# bluz_gw_v1.net
KiCad netlist of a schematic drawn in EAGLE
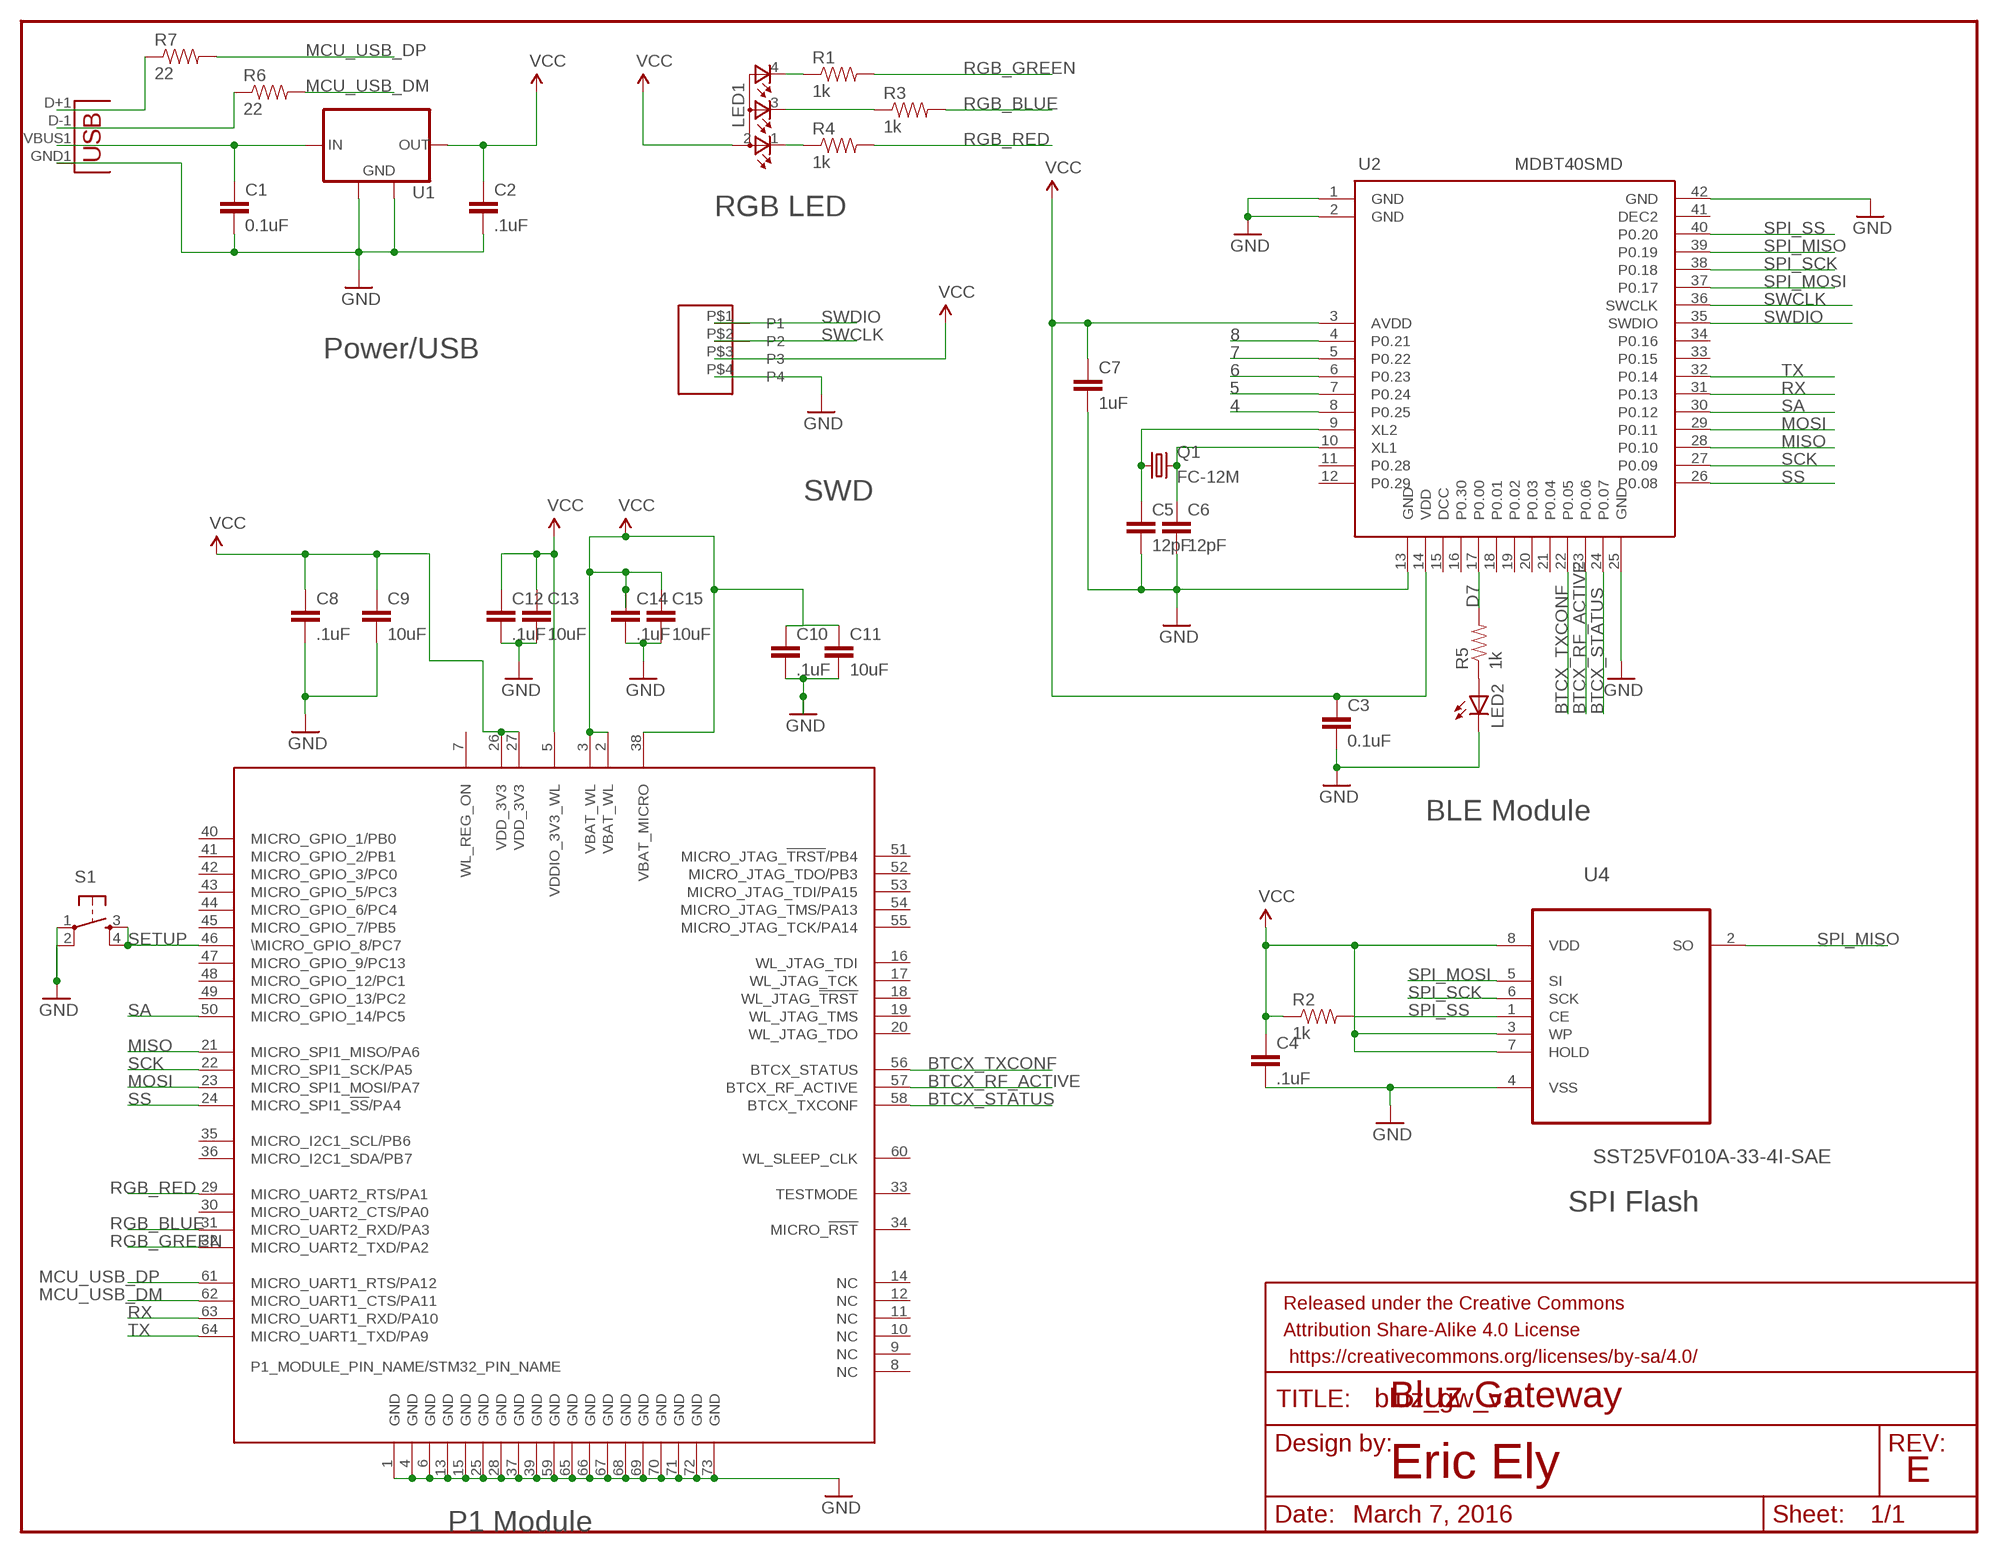
[diagram p0: schematic, sheet 1]

(export (version "E")
  (design (tool "Eeschema 10.0.6"))
  (components
    (comp (ref "C1")
      (value "0.1uF")
      (footprint "eagle-import:0603-CAP")
      (libsource (lib "eagle-import") (part "SparkFun-Passives_CAP0603-CAP"))
    )
    (comp (ref "C2")
      (value ".1uF")
      (footprint "eagle-import:0603-CAP")
      (libsource (lib "eagle-import") (part "CAP0603-CAP"))
    )
    (comp (ref "C3")
      (value "0.1uF")
      (footprint "eagle-import:0603-CAP")
      (libsource (lib "eagle-import") (part "CAP0603-CAP"))
    )
    (comp (ref "C4")
      (value ".1uF")
      (footprint "eagle-import:0603-CAP")
      (libsource (lib "eagle-import") (part "CAP0603-CAP"))
    )
    (comp (ref "C5")
      (value "12pF")
      (footprint "eagle-import:0603-CAP")
      (libsource (lib "eagle-import") (part "SparkFun-Passives_CAP0603-CAP"))
    )
    (comp (ref "C6")
      (value "12pF")
      (footprint "eagle-import:0603-CAP")
      (libsource (lib "eagle-import") (part "SparkFun-Passives_CAP0603-CAP"))
    )
    (comp (ref "C7")
      (value "1uF")
      (footprint "eagle-import:0603-CAP")
      (libsource (lib "eagle-import") (part "CAP0603-CAP"))
    )
    (comp (ref "C8")
      (value ".1uF")
      (footprint "eagle-import:0603-CAP")
      (libsource (lib "eagle-import") (part "CAP0603-CAP"))
    )
    (comp (ref "C9")
      (value "10uF")
      (footprint "eagle-import:0603-CAP")
      (libsource (lib "eagle-import") (part "CAP0603-CAP"))
    )
    (comp (ref "C10")
      (value ".1uF")
      (footprint "eagle-import:0603-CAP")
      (libsource (lib "eagle-import") (part "CAP0603-CAP"))
    )
    (comp (ref "C11")
      (value "10uF")
      (footprint "eagle-import:0603-CAP")
      (libsource (lib "eagle-import") (part "CAP0603-CAP"))
    )
    (comp (ref "C12")
      (value ".1uF")
      (footprint "eagle-import:0603-CAP")
      (libsource (lib "eagle-import") (part "CAP0603-CAP"))
    )
    (comp (ref "C13")
      (value "10uF")
      (footprint "eagle-import:0603-CAP")
      (libsource (lib "eagle-import") (part "CAP0603-CAP"))
    )
    (comp (ref "C14")
      (value ".1uF")
      (footprint "eagle-import:0603-CAP")
      (libsource (lib "eagle-import") (part "CAP0603-CAP"))
    )
    (comp (ref "C15")
      (value "10uF")
      (footprint "eagle-import:0603-CAP")
      (libsource (lib "eagle-import") (part "CAP0603-CAP"))
    )
    (comp (ref "FRAME1")
      (value "FRAME-LETTER")
      (footprint "eagle-import:CREATIVE_COMMONS")
      (libsource (lib "eagle-import") (part "FRAME-LETTER"))
    )
    (comp (ref "JP2")
      (value "USBA-SMD-MALE")
      (footprint "eagle-import:USB-A-SMT-MALE")
      (libsource (lib "eagle-import") (part "USBA-SMD-MALE"))
    )
    (comp (ref "LED1")
      (value "TOPLED-3PLCC")
      (footprint "eagle-import:P-LCC-4-3")
      (libsource (lib "eagle-import") (part "TOPLED-3PLCC"))
    )
    (comp (ref "LED2")
      (value "LEDCHIP-LED0603")
      (footprint "eagle-import:CHIP-LED0603")
      (libsource (lib "eagle-import") (part "LEDCHIP-LED0603"))
    )
    (comp (ref "Q1")
      (value "FC-12M")
      (footprint "eagle-import:FC-12M")
      (libsource (lib "eagle-import") (part "FC-12M"))
    )
    (comp (ref "R1")
      (value "1k")
      (footprint "eagle-import:0603-RES")
      (libsource (lib "eagle-import") (part "RESISTOR0603-RES"))
    )
    (comp (ref "R2")
      (value "1k")
      (footprint "eagle-import:0603-RES")
      (libsource (lib "eagle-import") (part "RESISTOR0603-RES"))
    )
    (comp (ref "R3")
      (value "1k")
      (footprint "eagle-import:0603-RES")
      (libsource (lib "eagle-import") (part "RESISTOR0603-RES"))
    )
    (comp (ref "R4")
      (value "1k")
      (footprint "eagle-import:0603-RES")
      (libsource (lib "eagle-import") (part "RESISTOR0603-RES"))
    )
    (comp (ref "R5")
      (value "1k")
      (footprint "eagle-import:0603-RES")
      (libsource (lib "eagle-import") (part "RESISTOR0603-RES"))
    )
    (comp (ref "R6")
      (value "22")
      (footprint "eagle-import:0603-RES")
      (libsource (lib "eagle-import") (part "RESISTOR0603-RES"))
    )
    (comp (ref "R7")
      (value "22")
      (footprint "eagle-import:0603-RES")
      (libsource (lib "eagle-import") (part "RESISTOR0603-RES"))
    )
    (comp (ref "S1")
      (value "TAC_SWITCHSMD")
      (footprint "eagle-import:TACTILE_SWITCH_SMD")
      (libsource (lib "eagle-import") (part "TAC_SWITCHSMD"))
    )
    (comp (ref "U$3")
      (value "POGO_CONNECTORPOGO_CONNECTOR")
      (footprint "eagle-import:POGO_CONNECTER")
      (libsource (lib "eagle-import") (part "POGO_CONNECTORPOGO_CONNECTOR"))
    )
    (comp (ref "U1")
      (value "MCP1825S-SOT223")
      (footprint "eagle-import:SOT223")
      (libsource (lib "eagle-import") (part "MCP1825S-SOT223"))
    )
    (comp (ref "U2")
      (value "MDBT40SMD")
      (footprint "eagle-import:MDBT40")
      (libsource (lib "eagle-import") (part "MDBT40SMD"))
    )
    (comp (ref "U3")
      (value "WM-N-BM-14")
      (footprint "eagle-import:WM-N-BM-14")
      (libsource (lib "eagle-import") (part "WM-N-BM-14"))
    )
    (comp (ref "U4")
      (value "SST25VF010A-33-4I-SAE")
      (footprint "eagle-import:SOIC127P600X175-8N")
      (libsource (lib "eagle-import") (part "SST25VF010A-33-4I-SAE"))
    )
  )
  (nets
    (net (code "1") (name "/4") (class "Default")
      (node (ref "U2") (pin "8") (pinfunction "P0.25_8") (pintype "bidirectional"))
    )
    (net (code "2") (name "/5") (class "Default")
      (node (ref "U2") (pin "7") (pinfunction "P0.24_7") (pintype "bidirectional"))
    )
    (net (code "3") (name "/6") (class "Default")
      (node (ref "U2") (pin "6") (pinfunction "P0.23_6") (pintype "bidirectional"))
    )
    (net (code "4") (name "/7") (class "Default")
      (node (ref "U2") (pin "5") (pinfunction "P0.22_5") (pintype "bidirectional"))
    )
    (net (code "5") (name "/8") (class "Default")
      (node (ref "U2") (pin "4") (pinfunction "P0.21_4") (pintype "bidirectional"))
    )
    (net (code "6") (name "/BTCX_RF_ACTIVE") (class "Default")
      (node (ref "U2") (pin "23") (pinfunction "P0.06_23") (pintype "bidirectional"))
      (node (ref "U3") (pin "57") (pinfunction "BTCX_RF_ACTIVE_57") (pintype "bidirectional"))
    )
    (net (code "7") (name "/BTCX_STATUS") (class "Default")
      (node (ref "U2") (pin "24") (pinfunction "P0.07_24") (pintype "bidirectional"))
      (node (ref "U3") (pin "58") (pinfunction "BTCX_TXCONF_58") (pintype "bidirectional"))
    )
    (net (code "8") (name "/BTCX_TXCONF") (class "Default")
      (node (ref "U2") (pin "22") (pinfunction "P0.05_22") (pintype "bidirectional"))
      (node (ref "U3") (pin "56") (pinfunction "BTCX_STATUS_56") (pintype "bidirectional"))
    )
    (net (code "9") (name "/D7") (class "Default")
      (node (ref "R5") (pin "2") (pinfunction "2_2") (pintype "passive"))
      (node (ref "U2") (pin "17") (pinfunction "P0.00_17") (pintype "bidirectional"))
    )
    (net (code "10") (name "/MCU_USB_DM") (class "Default")
      (node (ref "R6") (pin "2") (pinfunction "2_2") (pintype "passive"))
      (node (ref "U3") (pin "62") (pinfunction "MICRO_UART1_CTS/PA11_62") (pintype "bidirectional"))
    )
    (net (code "11") (name "/MCU_USB_DP") (class "Default")
      (node (ref "R7") (pin "2") (pinfunction "2_2") (pintype "passive"))
      (node (ref "U3") (pin "61") (pinfunction "MICRO_UART1_RTS/PA12_61") (pintype "bidirectional"))
    )
    (net (code "12") (name "/MISO") (class "Default")
      (node (ref "U2") (pin "28") (pinfunction "P0.10_28") (pintype "bidirectional"))
      (node (ref "U3") (pin "21") (pinfunction "MICRO_SPI1_MISO/PA6_21") (pintype "bidirectional"))
    )
    (net (code "13") (name "/MOSI") (class "Default")
      (node (ref "U2") (pin "29") (pinfunction "P0.11_29") (pintype "bidirectional"))
      (node (ref "U3") (pin "23") (pinfunction "MICRO_SPI1_MOSI/PA7_23") (pintype "bidirectional"))
    )
    (net (code "14") (name "/RGB_BLUE") (class "Default")
      (node (ref "R3") (pin "2") (pinfunction "2_2") (pintype "passive"))
      (node (ref "U3") (pin "31") (pinfunction "MICRO_UART2_RXD/PA3_31") (pintype "bidirectional"))
    )
    (net (code "15") (name "/RGB_GREEN") (class "Default")
      (node (ref "R1") (pin "2") (pinfunction "2_2") (pintype "passive"))
      (node (ref "U3") (pin "32") (pinfunction "MICRO_UART2_TXD/PA2_32") (pintype "bidirectional"))
    )
    (net (code "16") (name "/RGB_RED") (class "Default")
      (node (ref "R4") (pin "2") (pinfunction "2_2") (pintype "passive"))
      (node (ref "U3") (pin "29") (pinfunction "MICRO_UART2_RTS/PA1_29") (pintype "bidirectional"))
    )
    (net (code "17") (name "/RX") (class "Default")
      (node (ref "U2") (pin "31") (pinfunction "P0.13_31") (pintype "bidirectional"))
      (node (ref "U3") (pin "63") (pinfunction "MICRO_UART1_RXD/PA10_63") (pintype "bidirectional"))
    )
    (net (code "18") (name "/SA") (class "Default")
      (node (ref "U2") (pin "30") (pinfunction "P0.12_30") (pintype "bidirectional"))
      (node (ref "U3") (pin "50") (pinfunction "MICRO_GPIO_14/PC5_50") (pintype "bidirectional"))
    )
    (net (code "19") (name "/SCK") (class "Default")
      (node (ref "U2") (pin "27") (pinfunction "P0.09_27") (pintype "bidirectional"))
      (node (ref "U3") (pin "22") (pinfunction "MICRO_SPI1_SCK/PA5_22") (pintype "bidirectional"))
    )
    (net (code "20") (name "/SETUP") (class "Default")
      (node (ref "S1") (pin "3") (pinfunction "3_3") (pintype "passive"))
      (node (ref "S1") (pin "4") (pinfunction "4_4") (pintype "passive"))
      (node (ref "U3") (pin "46") (pinfunction "\\MICRO_GPIO_8/PC7_46") (pintype "bidirectional"))
    )
    (net (code "21") (name "/SPI_MISO") (class "Default")
      (node (ref "U2") (pin "39") (pinfunction "P0.19_39") (pintype "bidirectional"))
      (node (ref "U4") (pin "2") (pinfunction "SO_2") (pintype "output"))
    )
    (net (code "22") (name "/SPI_MOSI") (class "Default")
      (node (ref "U2") (pin "37") (pinfunction "P0.17_37") (pintype "bidirectional"))
      (node (ref "U4") (pin "5") (pinfunction "SI_5") (pintype "input"))
    )
    (net (code "23") (name "/SPI_SCK") (class "Default")
      (node (ref "U2") (pin "38") (pinfunction "P0.18_38") (pintype "bidirectional"))
      (node (ref "U4") (pin "6") (pinfunction "SCK_6") (pintype "input"))
    )
    (net (code "24") (name "/SPI_SS") (class "Default")
      (node (ref "R2") (pin "2") (pinfunction "2_2") (pintype "passive"))
      (node (ref "U2") (pin "40") (pinfunction "P0.20_40") (pintype "bidirectional"))
      (node (ref "U4") (pin "1") (pinfunction "CE_1") (pintype "input"))
    )
    (net (code "25") (name "/SS") (class "Default")
      (node (ref "U2") (pin "26") (pinfunction "P0.08_26") (pintype "bidirectional"))
      (node (ref "U3") (pin "24") (pinfunction "MICRO_SPI1_~{SS}/PA4_24") (pintype "bidirectional"))
    )
    (net (code "26") (name "/SWCLK") (class "Default")
      (node (ref "U$3") (pin "P$2") (pinfunction "P2_P$2") (pintype "bidirectional"))
      (node (ref "U2") (pin "36") (pinfunction "SWCLK_36") (pintype "bidirectional"))
    )
    (net (code "27") (name "/SWDIO") (class "Default")
      (node (ref "U$3") (pin "P$1") (pinfunction "P1_P$1") (pintype "bidirectional"))
      (node (ref "U2") (pin "35") (pinfunction "SWDIO_35") (pintype "bidirectional"))
    )
    (net (code "28") (name "/TX") (class "Default")
      (node (ref "U2") (pin "32") (pinfunction "P0.14_32") (pintype "bidirectional"))
      (node (ref "U3") (pin "64") (pinfunction "MICRO_UART1_TXD/PA9_64") (pintype "bidirectional"))
    )
    (net (code "29") (name "GND") (class "Default")
      (node (ref "C1") (pin "2") (pinfunction "2_2") (pintype "passive"))
      (node (ref "C10") (pin "2") (pinfunction "2_2") (pintype "passive"))
      (node (ref "C11") (pin "2") (pinfunction "2_2") (pintype "passive"))
      (node (ref "C12") (pin "2") (pinfunction "2_2") (pintype "passive"))
      (node (ref "C13") (pin "2") (pinfunction "2_2") (pintype "passive"))
      (node (ref "C14") (pin "2") (pinfunction "2_2") (pintype "passive"))
      (node (ref "C15") (pin "2") (pinfunction "2_2") (pintype "passive"))
      (node (ref "C2") (pin "2") (pinfunction "2_2") (pintype "passive"))
      (node (ref "C3") (pin "2") (pinfunction "2_2") (pintype "passive"))
      (node (ref "C4") (pin "2") (pinfunction "2_2") (pintype "passive"))
      (node (ref "C5") (pin "2") (pinfunction "2_2") (pintype "passive"))
      (node (ref "C6") (pin "2") (pinfunction "2_2") (pintype "passive"))
      (node (ref "C7") (pin "2") (pinfunction "2_2") (pintype "passive"))
      (node (ref "C8") (pin "2") (pinfunction "2_2") (pintype "passive"))
      (node (ref "C9") (pin "2") (pinfunction "2_2") (pintype "passive"))
      (node (ref "JP2") (pin "GND1") (pinfunction "GND_GND1") (pintype "bidirectional"))
      (node (ref "LED2") (pin "C") (pinfunction "C_C") (pintype "passive"))
      (node (ref "S1") (pin "1") (pinfunction "1_1") (pintype "passive"))
      (node (ref "S1") (pin "2") (pinfunction "2_2") (pintype "passive"))
      (node (ref "U$3") (pin "P$4") (pinfunction "P4_P$4") (pintype "bidirectional"))
      (node (ref "U1") (pin "2") (pinfunction "GND_2") (pintype "power_in"))
      (node (ref "U1") (pin "4") (pinfunction "GND_4") (pintype "power_in"))
      (node (ref "U2") (pin "1") (pinfunction "GND_1") (pintype "bidirectional"))
      (node (ref "U2") (pin "13") (pinfunction "GND_13") (pintype "bidirectional"))
      (node (ref "U2") (pin "2") (pinfunction "GND_2") (pintype "bidirectional"))
      (node (ref "U2") (pin "25") (pinfunction "GND_25") (pintype "bidirectional"))
      (node (ref "U2") (pin "42") (pinfunction "GND_42") (pintype "bidirectional"))
      (node (ref "U3") (pin "1") (pinfunction "GND_1") (pintype "bidirectional"))
      (node (ref "U3") (pin "13") (pinfunction "GND_13") (pintype "bidirectional"))
      (node (ref "U3") (pin "15") (pinfunction "GND_15") (pintype "bidirectional"))
      (node (ref "U3") (pin "25") (pinfunction "GND_25") (pintype "bidirectional"))
      (node (ref "U3") (pin "28") (pinfunction "GND_28") (pintype "bidirectional"))
      (node (ref "U3") (pin "37") (pinfunction "GND_37") (pintype "bidirectional"))
      (node (ref "U3") (pin "39") (pinfunction "GND_39") (pintype "bidirectional"))
      (node (ref "U3") (pin "4") (pinfunction "GND_4") (pintype "bidirectional"))
      (node (ref "U3") (pin "59") (pinfunction "GND_59") (pintype "bidirectional"))
      (node (ref "U3") (pin "6") (pinfunction "GND_6") (pintype "bidirectional"))
      (node (ref "U3") (pin "65") (pinfunction "GND_65") (pintype "bidirectional"))
      (node (ref "U3") (pin "66") (pinfunction "GND_66") (pintype "bidirectional"))
      (node (ref "U3") (pin "67") (pinfunction "GND_67") (pintype "bidirectional"))
      (node (ref "U3") (pin "68") (pinfunction "GND_68") (pintype "bidirectional"))
      (node (ref "U3") (pin "69") (pinfunction "GND_69") (pintype "bidirectional"))
      (node (ref "U3") (pin "70") (pinfunction "GND_70") (pintype "bidirectional"))
      (node (ref "U3") (pin "71") (pinfunction "GND_71") (pintype "bidirectional"))
      (node (ref "U3") (pin "72") (pinfunction "GND_72") (pintype "bidirectional"))
      (node (ref "U3") (pin "73") (pinfunction "GND_73") (pintype "bidirectional"))
      (node (ref "U4") (pin "4") (pinfunction "VSS_4") (pintype "passive"))
    )
    (net (code "30") (name "Net-(JP2-D+)") (class "Default")
      (node (ref "JP2") (pin "D+1") (pinfunction "D+_D+1") (pintype "bidirectional"))
      (node (ref "R7") (pin "1") (pinfunction "1_1") (pintype "passive"))
    )
    (net (code "31") (name "Net-(JP2-D-)") (class "Default")
      (node (ref "JP2") (pin "D-1") (pinfunction "D-_D-1") (pintype "bidirectional"))
      (node (ref "R6") (pin "1") (pinfunction "1_1") (pintype "passive"))
    )
    (net (code "32") (name "Net-(JP2-VBUS)") (class "Default")
      (node (ref "C1") (pin "1") (pinfunction "1_1") (pintype "passive"))
      (node (ref "JP2") (pin "VBUS1") (pinfunction "VBUS_VBUS1") (pintype "bidirectional"))
      (node (ref "U1") (pin "1") (pinfunction "IN_1") (pintype "input"))
    )
    (net (code "33") (name "Net-(LED1-CBLUE)") (class "Default")
      (node (ref "LED1") (pin "3") (pinfunction "CBLUE_3") (pintype "passive"))
      (node (ref "R3") (pin "1") (pinfunction "1_1") (pintype "passive"))
    )
    (net (code "34") (name "Net-(LED1-CGREEN)") (class "Default")
      (node (ref "LED1") (pin "4") (pinfunction "CGREEN_4") (pintype "passive"))
      (node (ref "R1") (pin "1") (pinfunction "1_1") (pintype "passive"))
    )
    (net (code "35") (name "Net-(LED1-CRED)") (class "Default")
      (node (ref "LED1") (pin "1") (pinfunction "CRED_1") (pintype "passive"))
      (node (ref "R4") (pin "1") (pinfunction "1_1") (pintype "passive"))
    )
    (net (code "36") (name "Net-(LED2-PadA)") (class "Default")
      (node (ref "LED2") (pin "A") (pinfunction "A_A") (pintype "passive"))
      (node (ref "R5") (pin "1") (pinfunction "1_1") (pintype "passive"))
    )
    (net (code "37") (name "Net-(U2-XL1)") (class "Default")
      (node (ref "C6") (pin "1") (pinfunction "1_1") (pintype "passive"))
      (node (ref "Q1") (pin "2") (pinfunction "2_2") (pintype "passive"))
      (node (ref "U2") (pin "10") (pinfunction "XL1_10") (pintype "bidirectional"))
    )
    (net (code "38") (name "Net-(U2-XL2)") (class "Default")
      (node (ref "C5") (pin "1") (pinfunction "1_1") (pintype "passive"))
      (node (ref "Q1") (pin "1") (pinfunction "1_1") (pintype "passive"))
      (node (ref "U2") (pin "9") (pinfunction "XL2_9") (pintype "bidirectional"))
    )
    (net (code "39") (name "VCC") (class "Default")
      (node (ref "C10") (pin "1") (pinfunction "1_1") (pintype "passive"))
      (node (ref "C11") (pin "1") (pinfunction "1_1") (pintype "passive"))
      (node (ref "C12") (pin "1") (pinfunction "1_1") (pintype "passive"))
      (node (ref "C13") (pin "1") (pinfunction "1_1") (pintype "passive"))
      (node (ref "C14") (pin "1") (pinfunction "1_1") (pintype "passive"))
      (node (ref "C15") (pin "1") (pinfunction "1_1") (pintype "passive"))
      (node (ref "C2") (pin "1") (pinfunction "1_1") (pintype "passive"))
      (node (ref "C3") (pin "1") (pinfunction "1_1") (pintype "passive"))
      (node (ref "C4") (pin "1") (pinfunction "1_1") (pintype "passive"))
      (node (ref "C7") (pin "1") (pinfunction "1_1") (pintype "passive"))
      (node (ref "C8") (pin "1") (pinfunction "1_1") (pintype "passive"))
      (node (ref "C9") (pin "1") (pinfunction "1_1") (pintype "passive"))
      (node (ref "LED1") (pin "2") (pinfunction "A2_2") (pintype "passive"))
      (node (ref "R2") (pin "1") (pinfunction "1_1") (pintype "passive"))
      (node (ref "U$3") (pin "P$3") (pinfunction "P3_P$3") (pintype "bidirectional"))
      (node (ref "U1") (pin "3") (pinfunction "OUT_3") (pintype "output"))
      (node (ref "U2") (pin "14") (pinfunction "VDD_14") (pintype "bidirectional"))
      (node (ref "U2") (pin "3") (pinfunction "AVDD_3") (pintype "bidirectional"))
      (node (ref "U3") (pin "2") (pinfunction "VBAT_WL_2") (pintype "bidirectional"))
      (node (ref "U3") (pin "26") (pinfunction "VDD_3V3_26") (pintype "bidirectional"))
      (node (ref "U3") (pin "27") (pinfunction "VDD_3V3_27") (pintype "bidirectional"))
      (node (ref "U3") (pin "3") (pinfunction "VBAT_WL_3") (pintype "bidirectional"))
      (node (ref "U3") (pin "38") (pinfunction "VBAT_MICRO_38") (pintype "bidirectional"))
      (node (ref "U3") (pin "5") (pinfunction "VDDIO_3V3_WL_5") (pintype "bidirectional"))
      (node (ref "U4") (pin "3") (pinfunction "WP_3") (pintype "input"))
      (node (ref "U4") (pin "7") (pinfunction "HOLD_7") (pintype "input"))
      (node (ref "U4") (pin "8") (pinfunction "VDD_8") (pintype "power_in"))
    )
    (net (code "40") (name "unconnected-(U2-DCC-Pad15)") (class "Default")
      (node (ref "U2") (pin "15") (pinfunction "DCC_15") (pintype "bidirectional"))
    )
    (net (code "41") (name "unconnected-(U2-DEC2-Pad41)") (class "Default")
      (node (ref "U2") (pin "41") (pinfunction "DEC2_41") (pintype "bidirectional"))
    )
    (net (code "42") (name "unconnected-(U2-P0.01-Pad18)") (class "Default")
      (node (ref "U2") (pin "18") (pinfunction "P0.01_18") (pintype "bidirectional"))
    )
    (net (code "43") (name "unconnected-(U2-P0.02-Pad19)") (class "Default")
      (node (ref "U2") (pin "19") (pinfunction "P0.02_19") (pintype "bidirectional"))
    )
    (net (code "44") (name "unconnected-(U2-P0.03-Pad20)") (class "Default")
      (node (ref "U2") (pin "20") (pinfunction "P0.03_20") (pintype "bidirectional"))
    )
    (net (code "45") (name "unconnected-(U2-P0.04-Pad21)") (class "Default")
      (node (ref "U2") (pin "21") (pinfunction "P0.04_21") (pintype "bidirectional"))
    )
    (net (code "46") (name "unconnected-(U2-P0.15-Pad33)") (class "Default")
      (node (ref "U2") (pin "33") (pinfunction "P0.15_33") (pintype "bidirectional"))
    )
    (net (code "47") (name "unconnected-(U2-P0.16-Pad34)") (class "Default")
      (node (ref "U2") (pin "34") (pinfunction "P0.16_34") (pintype "bidirectional"))
    )
    (net (code "48") (name "unconnected-(U2-P0.28-Pad11)") (class "Default")
      (node (ref "U2") (pin "11") (pinfunction "P0.28_11") (pintype "bidirectional"))
    )
    (net (code "49") (name "unconnected-(U2-P0.29-Pad12)") (class "Default")
      (node (ref "U2") (pin "12") (pinfunction "P0.29_12") (pintype "bidirectional"))
    )
    (net (code "50") (name "unconnected-(U2-P0.30-Pad16)") (class "Default")
      (node (ref "U2") (pin "16") (pinfunction "P0.30_16") (pintype "bidirectional"))
    )
    (net (code "51") (name "unconnected-(U3-MICRO_GPIO_1{slash}PB0-Pad40)") (class "Default")
      (node (ref "U3") (pin "40") (pinfunction "MICRO_GPIO_1/PB0_40") (pintype "bidirectional"))
    )
    (net (code "52") (name "unconnected-(U3-MICRO_GPIO_2{slash}PB1-Pad41)") (class "Default")
      (node (ref "U3") (pin "41") (pinfunction "MICRO_GPIO_2/PB1_41") (pintype "bidirectional"))
    )
    (net (code "53") (name "unconnected-(U3-MICRO_GPIO_3{slash}PC0-Pad42)") (class "Default")
      (node (ref "U3") (pin "42") (pinfunction "MICRO_GPIO_3/PC0_42") (pintype "bidirectional"))
    )
    (net (code "54") (name "unconnected-(U3-MICRO_GPIO_5{slash}PC3-Pad43)") (class "Default")
      (node (ref "U3") (pin "43") (pinfunction "MICRO_GPIO_5/PC3_43") (pintype "bidirectional"))
    )
    (net (code "55") (name "unconnected-(U3-MICRO_GPIO_6{slash}PC4-Pad44)") (class "Default")
      (node (ref "U3") (pin "44") (pinfunction "MICRO_GPIO_6/PC4_44") (pintype "bidirectional"))
    )
    (net (code "56") (name "unconnected-(U3-MICRO_GPIO_7{slash}PB5-Pad45)") (class "Default")
      (node (ref "U3") (pin "45") (pinfunction "MICRO_GPIO_7/PB5_45") (pintype "bidirectional"))
    )
    (net (code "57") (name "unconnected-(U3-MICRO_GPIO_9{slash}PC13-Pad47)") (class "Default")
      (node (ref "U3") (pin "47") (pinfunction "MICRO_GPIO_9/PC13_47") (pintype "bidirectional"))
    )
    (net (code "58") (name "unconnected-(U3-MICRO_GPIO_12{slash}PC1-Pad48)") (class "Default")
      (node (ref "U3") (pin "48") (pinfunction "MICRO_GPIO_12/PC1_48") (pintype "bidirectional"))
    )
    (net (code "59") (name "unconnected-(U3-MICRO_GPIO_13{slash}PC2-Pad49)") (class "Default")
      (node (ref "U3") (pin "49") (pinfunction "MICRO_GPIO_13/PC2_49") (pintype "bidirectional"))
    )
    (net (code "60") (name "unconnected-(U3-MICRO_I2C1_SCL{slash}PB6-Pad35)") (class "Default")
      (node (ref "U3") (pin "35") (pinfunction "MICRO_I2C1_SCL/PB6_35") (pintype "bidirectional"))
    )
    (net (code "61") (name "unconnected-(U3-MICRO_I2C1_SDA{slash}PB7-Pad36)") (class "Default")
      (node (ref "U3") (pin "36") (pinfunction "MICRO_I2C1_SDA/PB7_36") (pintype "bidirectional"))
    )
    (net (code "62") (name "unconnected-(U3-MICRO_JTAG_TCK{slash}PA14-Pad55)") (class "Default")
      (node (ref "U3") (pin "55") (pinfunction "MICRO_JTAG_TCK/PA14_55") (pintype "bidirectional"))
    )
    (net (code "63") (name "unconnected-(U3-MICRO_JTAG_TDI{slash}PA15-Pad53)") (class "Default")
      (node (ref "U3") (pin "53") (pinfunction "MICRO_JTAG_TDI/PA15_53") (pintype "bidirectional"))
    )
    (net (code "64") (name "unconnected-(U3-MICRO_JTAG_TDO{slash}PB3-Pad52)") (class "Default")
      (node (ref "U3") (pin "52") (pinfunction "MICRO_JTAG_TDO/PB3_52") (pintype "bidirectional"))
    )
    (net (code "65") (name "unconnected-(U3-MICRO_JTAG_TMS{slash}PA13-Pad54)") (class "Default")
      (node (ref "U3") (pin "54") (pinfunction "MICRO_JTAG_TMS/PA13_54") (pintype "bidirectional"))
    )
    (net (code "66") (name "unconnected-(U3-MICRO_JTAG_~{TRST}{slash}PB4-Pad51)") (class "Default")
      (node (ref "U3") (pin "51") (pinfunction "MICRO_JTAG_~{TRST}/PB4_51") (pintype "bidirectional"))
    )
    (net (code "67") (name "unconnected-(U3-MICRO_UART2_CTS{slash}PA0-Pad30)") (class "Default")
      (node (ref "U3") (pin "30") (pinfunction "MICRO_UART2_CTS/PA0_30") (pintype "bidirectional"))
    )
    (net (code "68") (name "unconnected-(U3-MICRO_~{RST}-Pad34)") (class "Default")
      (node (ref "U3") (pin "34") (pinfunction "MICRO_~{RST}_34") (pintype "bidirectional"))
    )
    (net (code "69") (name "unconnected-(U3-NC-Pad8)") (class "Default")
      (node (ref "U3") (pin "8") (pinfunction "NC_8") (pintype "bidirectional"))
    )
    (net (code "70") (name "unconnected-(U3-NC-Pad9)") (class "Default")
      (node (ref "U3") (pin "9") (pinfunction "NC_9") (pintype "bidirectional"))
    )
    (net (code "71") (name "unconnected-(U3-NC-Pad10)") (class "Default")
      (node (ref "U3") (pin "10") (pinfunction "NC_10") (pintype "bidirectional"))
    )
    (net (code "72") (name "unconnected-(U3-NC-Pad11)") (class "Default")
      (node (ref "U3") (pin "11") (pinfunction "NC_11") (pintype "bidirectional"))
    )
    (net (code "73") (name "unconnected-(U3-NC-Pad12)") (class "Default")
      (node (ref "U3") (pin "12") (pinfunction "NC_12") (pintype "bidirectional"))
    )
    (net (code "74") (name "unconnected-(U3-NC-Pad14)") (class "Default")
      (node (ref "U3") (pin "14") (pinfunction "NC_14") (pintype "bidirectional"))
    )
    (net (code "75") (name "unconnected-(U3-TESTMODE-Pad33)") (class "Default")
      (node (ref "U3") (pin "33") (pinfunction "TESTMODE_33") (pintype "bidirectional"))
    )
    (net (code "76") (name "unconnected-(U3-WL_JTAG_TCK-Pad17)") (class "Default")
      (node (ref "U3") (pin "17") (pinfunction "WL_JTAG_TCK_17") (pintype "bidirectional"))
    )
    (net (code "77") (name "unconnected-(U3-WL_JTAG_TDI-Pad16)") (class "Default")
      (node (ref "U3") (pin "16") (pinfunction "WL_JTAG_TDI_16") (pintype "bidirectional"))
    )
    (net (code "78") (name "unconnected-(U3-WL_JTAG_TDO-Pad20)") (class "Default")
      (node (ref "U3") (pin "20") (pinfunction "WL_JTAG_TDO_20") (pintype "bidirectional"))
    )
    (net (code "79") (name "unconnected-(U3-WL_JTAG_TMS-Pad19)") (class "Default")
      (node (ref "U3") (pin "19") (pinfunction "WL_JTAG_TMS_19") (pintype "bidirectional"))
    )
    (net (code "80") (name "unconnected-(U3-WL_JTAG_~{TRST}-Pad18)") (class "Default")
      (node (ref "U3") (pin "18") (pinfunction "WL_JTAG_~{TRST}_18") (pintype "bidirectional"))
    )
    (net (code "81") (name "unconnected-(U3-WL_REG_ON-Pad7)") (class "Default")
      (node (ref "U3") (pin "7") (pinfunction "WL_REG_ON_7") (pintype "bidirectional"))
    )
    (net (code "82") (name "unconnected-(U3-WL_SLEEP_CLK-Pad60)") (class "Default")
      (node (ref "U3") (pin "60") (pinfunction "WL_SLEEP_CLK_60") (pintype "bidirectional"))
    )
  )
)
